# OBKP_Effector_PCB.net
KiCad netlist of a schematic drawn in EAGLE
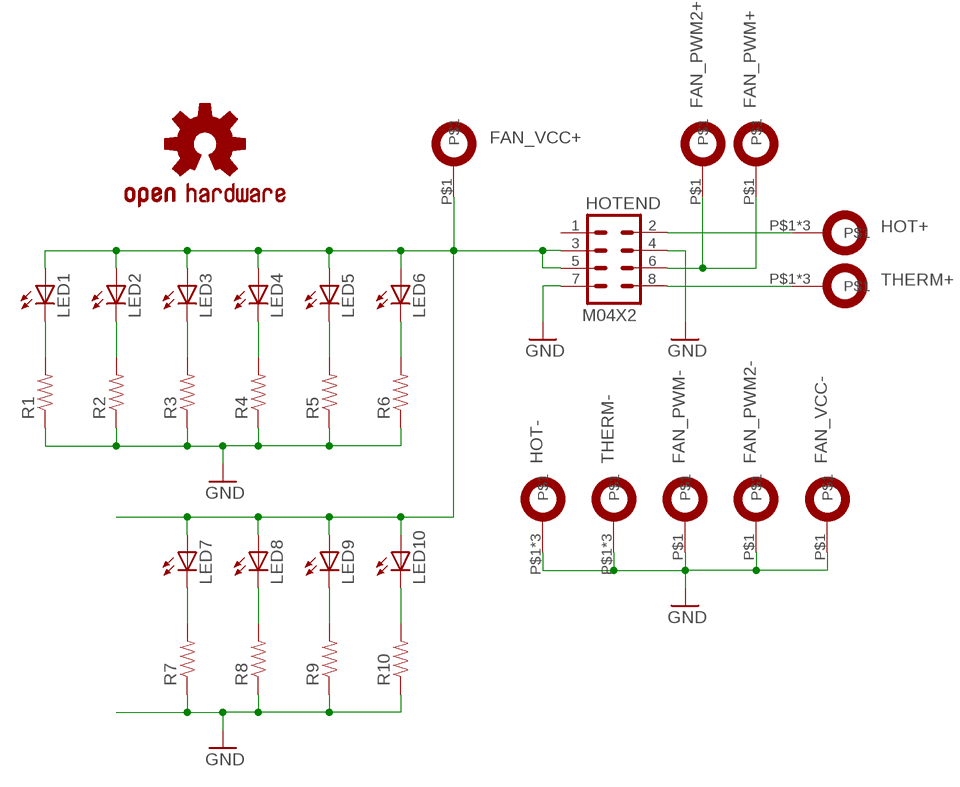
[diagram p0: schematic, sheet 1]

(export (version "E")
  (design (tool "Eeschema 10.0.6"))
  (components
    (comp (ref "FAN_PWM+")
      (value "LUG2.3")
      (footprint "eagle-import:2.3MM")
      (libsource (lib "eagle-import") (part "LUG2.3"))
    )
    (comp (ref "FAN_PWM-")
      (value "LUG2.3")
      (footprint "eagle-import:2.3MM")
      (libsource (lib "eagle-import") (part "LUG2.3"))
    )
    (comp (ref "FAN_PWM2+")
      (value "LUG2.3")
      (footprint "eagle-import:2.3MM")
      (libsource (lib "eagle-import") (part "LUG2.3"))
    )
    (comp (ref "FAN_PWM2-")
      (value "LUG2.3")
      (footprint "eagle-import:2.3MM")
      (libsource (lib "eagle-import") (part "LUG2.3"))
    )
    (comp (ref "FAN_VCC+")
      (value "LUG2.3")
      (footprint "eagle-import:2.3MM")
      (libsource (lib "eagle-import") (part "LUG2.3"))
    )
    (comp (ref "FAN_VCC-")
      (value "LUG2.3")
      (footprint "eagle-import:2.3MM")
      (libsource (lib "eagle-import") (part "LUG2.3"))
    )
    (comp (ref "HOT+")
      (value "LUG3-X")
      (footprint "eagle-import:3MM")
      (libsource (lib "eagle-import") (part "LUG3-X"))
    )
    (comp (ref "HOT-")
      (value "LUG3-X")
      (footprint "eagle-import:3MM")
      (libsource (lib "eagle-import") (part "LUG3-X"))
    )
    (comp (ref "HOTEND")
      (value "M04X2")
      (footprint "eagle-import:2X4")
      (libsource (lib "eagle-import") (part "M04X2"))
    )
    (comp (ref "LED1")
      (value "LED0805")
      (footprint "eagle-import:CHIPLED_0805")
      (libsource (lib "eagle-import") (part "LED0805"))
    )
    (comp (ref "LED2")
      (value "LED0805")
      (footprint "eagle-import:CHIPLED_0805")
      (libsource (lib "eagle-import") (part "LED0805"))
    )
    (comp (ref "LED3")
      (value "LED0805")
      (footprint "eagle-import:CHIPLED_0805")
      (libsource (lib "eagle-import") (part "LED0805"))
    )
    (comp (ref "LED4")
      (value "LED0805")
      (footprint "eagle-import:CHIPLED_0805")
      (libsource (lib "eagle-import") (part "LED0805"))
    )
    (comp (ref "LED5")
      (value "LED0805")
      (footprint "eagle-import:CHIPLED_0805")
      (libsource (lib "eagle-import") (part "LED0805"))
    )
    (comp (ref "LED6")
      (value "LED0805")
      (footprint "eagle-import:CHIPLED_0805")
      (libsource (lib "eagle-import") (part "LED0805"))
    )
    (comp (ref "LED7")
      (value "LED0805")
      (footprint "eagle-import:CHIPLED_0805")
      (libsource (lib "eagle-import") (part "LED0805"))
    )
    (comp (ref "LED8")
      (value "LED0805")
      (footprint "eagle-import:CHIPLED_0805")
      (libsource (lib "eagle-import") (part "LED0805"))
    )
    (comp (ref "LED9")
      (value "LED0805")
      (footprint "eagle-import:CHIPLED_0805")
      (libsource (lib "eagle-import") (part "LED0805"))
    )
    (comp (ref "LED10")
      (value "LED0805")
      (footprint "eagle-import:CHIPLED_0805")
      (libsource (lib "eagle-import") (part "LED0805"))
    )
    (comp (ref "LOGO1")
      (value "OSHW-LOGOS")
      (footprint "eagle-import:OSHW-LOGO-S")
      (libsource (lib "eagle-import") (part "OSHW-LOGOS"))
    )
    (comp (ref "R1")
      (value "RESISTOR0805-RES")
      (footprint "eagle-import:0805")
      (libsource (lib "eagle-import") (part "RESISTOR0805-RES"))
    )
    (comp (ref "R2")
      (value "RESISTOR0805-RES")
      (footprint "eagle-import:0805")
      (libsource (lib "eagle-import") (part "RESISTOR0805-RES"))
    )
    (comp (ref "R3")
      (value "RESISTOR0805-RES")
      (footprint "eagle-import:0805")
      (libsource (lib "eagle-import") (part "RESISTOR0805-RES"))
    )
    (comp (ref "R4")
      (value "RESISTOR0805-RES")
      (footprint "eagle-import:0805")
      (libsource (lib "eagle-import") (part "RESISTOR0805-RES"))
    )
    (comp (ref "R5")
      (value "RESISTOR0805-RES")
      (footprint "eagle-import:0805")
      (libsource (lib "eagle-import") (part "RESISTOR0805-RES"))
    )
    (comp (ref "R6")
      (value "RESISTOR0805-RES")
      (footprint "eagle-import:0805")
      (libsource (lib "eagle-import") (part "RESISTOR0805-RES"))
    )
    (comp (ref "R7")
      (value "RESISTOR0805-RES")
      (footprint "eagle-import:0805")
      (libsource (lib "eagle-import") (part "RESISTOR0805-RES"))
    )
    (comp (ref "R8")
      (value "RESISTOR0805-RES")
      (footprint "eagle-import:0805")
      (libsource (lib "eagle-import") (part "RESISTOR0805-RES"))
    )
    (comp (ref "R9")
      (value "RESISTOR0805-RES")
      (footprint "eagle-import:0805")
      (libsource (lib "eagle-import") (part "RESISTOR0805-RES"))
    )
    (comp (ref "R10")
      (value "RESISTOR0805-RES")
      (footprint "eagle-import:0805")
      (libsource (lib "eagle-import") (part "RESISTOR0805-RES"))
    )
    (comp (ref "THERM+")
      (value "LUG3-X")
      (footprint "eagle-import:3MM")
      (libsource (lib "eagle-import") (part "LUG3-X"))
    )
    (comp (ref "THERM-")
      (value "LUG3-X")
      (footprint "eagle-import:3MM")
      (libsource (lib "eagle-import") (part "LUG3-X"))
    )
  )
  (nets
    (net (code "1") (name "GND") (class "Default")
      (node (ref "FAN_PWM-") (pin "P$1") (pinfunction "P$1_P$1") (pintype "bidirectional"))
      (node (ref "FAN_PWM2-") (pin "P$1") (pinfunction "P$1_P$1") (pintype "bidirectional"))
      (node (ref "FAN_VCC-") (pin "P$1") (pinfunction "P$1_P$1") (pintype "bidirectional"))
      (node (ref "HOT-") (pin "P$1") (pinfunction "P$1_P$1") (pintype "bidirectional"))
      (node (ref "HOT-") (pin "P$2") (pinfunction "P$1_P$2") (pintype "bidirectional"))
      (node (ref "HOT-") (pin "P$3") (pinfunction "P$1_P$3") (pintype "bidirectional"))
      (node (ref "HOTEND") (pin "4") (pinfunction "4_4") (pintype "passive"))
      (node (ref "HOTEND") (pin "7") (pinfunction "7_7") (pintype "passive"))
      (node (ref "R1") (pin "1") (pinfunction "1_1") (pintype "passive"))
      (node (ref "R10") (pin "1") (pinfunction "1_1") (pintype "passive"))
      (node (ref "R2") (pin "1") (pinfunction "1_1") (pintype "passive"))
      (node (ref "R3") (pin "1") (pinfunction "1_1") (pintype "passive"))
      (node (ref "R4") (pin "1") (pinfunction "1_1") (pintype "passive"))
      (node (ref "R5") (pin "1") (pinfunction "1_1") (pintype "passive"))
      (node (ref "R6") (pin "1") (pinfunction "1_1") (pintype "passive"))
      (node (ref "R7") (pin "1") (pinfunction "1_1") (pintype "passive"))
      (node (ref "R8") (pin "1") (pinfunction "1_1") (pintype "passive"))
      (node (ref "R9") (pin "1") (pinfunction "1_1") (pintype "passive"))
      (node (ref "THERM-") (pin "P$1") (pinfunction "P$1_P$1") (pintype "bidirectional"))
      (node (ref "THERM-") (pin "P$2") (pinfunction "P$1_P$2") (pintype "bidirectional"))
      (node (ref "THERM-") (pin "P$3") (pinfunction "P$1_P$3") (pintype "bidirectional"))
    )
    (net (code "2") (name "Net-(FAN_PWM+-PadP$1)") (class "Default")
      (node (ref "FAN_PWM+") (pin "P$1") (pinfunction "P$1_P$1") (pintype "bidirectional"))
      (node (ref "FAN_PWM2+") (pin "P$1") (pinfunction "P$1_P$1") (pintype "bidirectional"))
      (node (ref "HOTEND") (pin "6") (pinfunction "6_6") (pintype "passive"))
    )
    (net (code "3") (name "Net-(FAN_VCC+-PadP$1)") (class "Default")
      (node (ref "FAN_VCC+") (pin "P$1") (pinfunction "P$1_P$1") (pintype "bidirectional"))
      (node (ref "HOTEND") (pin "3") (pinfunction "3_3") (pintype "passive"))
      (node (ref "HOTEND") (pin "5") (pinfunction "5_5") (pintype "passive"))
      (node (ref "LED1") (pin "A") (pinfunction "A_A") (pintype "passive"))
      (node (ref "LED10") (pin "A") (pinfunction "A_A") (pintype "passive"))
      (node (ref "LED2") (pin "A") (pinfunction "A_A") (pintype "passive"))
      (node (ref "LED3") (pin "A") (pinfunction "A_A") (pintype "passive"))
      (node (ref "LED4") (pin "A") (pinfunction "A_A") (pintype "passive"))
      (node (ref "LED5") (pin "A") (pinfunction "A_A") (pintype "passive"))
      (node (ref "LED6") (pin "A") (pinfunction "A_A") (pintype "passive"))
      (node (ref "LED7") (pin "A") (pinfunction "A_A") (pintype "passive"))
      (node (ref "LED8") (pin "A") (pinfunction "A_A") (pintype "passive"))
      (node (ref "LED9") (pin "A") (pinfunction "A_A") (pintype "passive"))
    )
    (net (code "4") (name "Net-(HOT+-P$1-PadP$2)") (class "Default")
      (node (ref "HOT+") (pin "P$1") (pinfunction "P$1_P$1") (pintype "bidirectional"))
      (node (ref "HOT+") (pin "P$2") (pinfunction "P$1_P$2") (pintype "bidirectional"))
      (node (ref "HOT+") (pin "P$3") (pinfunction "P$1_P$3") (pintype "bidirectional"))
      (node (ref "HOTEND") (pin "2") (pinfunction "2_2") (pintype "passive"))
    )
    (net (code "5") (name "Net-(HOTEND-Pad8)") (class "Default")
      (node (ref "HOTEND") (pin "8") (pinfunction "8_8") (pintype "passive"))
      (node (ref "THERM+") (pin "P$1") (pinfunction "P$1_P$1") (pintype "bidirectional"))
      (node (ref "THERM+") (pin "P$2") (pinfunction "P$1_P$2") (pintype "bidirectional"))
      (node (ref "THERM+") (pin "P$3") (pinfunction "P$1_P$3") (pintype "bidirectional"))
    )
    (net (code "6") (name "Net-(LED1-PadC)") (class "Default")
      (node (ref "LED1") (pin "C") (pinfunction "C_C") (pintype "passive"))
      (node (ref "R1") (pin "2") (pinfunction "2_2") (pintype "passive"))
    )
    (net (code "7") (name "Net-(LED2-PadC)") (class "Default")
      (node (ref "LED2") (pin "C") (pinfunction "C_C") (pintype "passive"))
      (node (ref "R2") (pin "2") (pinfunction "2_2") (pintype "passive"))
    )
    (net (code "8") (name "Net-(LED3-PadC)") (class "Default")
      (node (ref "LED3") (pin "C") (pinfunction "C_C") (pintype "passive"))
      (node (ref "R3") (pin "2") (pinfunction "2_2") (pintype "passive"))
    )
    (net (code "9") (name "Net-(LED4-PadC)") (class "Default")
      (node (ref "LED4") (pin "C") (pinfunction "C_C") (pintype "passive"))
      (node (ref "R4") (pin "2") (pinfunction "2_2") (pintype "passive"))
    )
    (net (code "10") (name "Net-(LED5-PadC)") (class "Default")
      (node (ref "LED5") (pin "C") (pinfunction "C_C") (pintype "passive"))
      (node (ref "R5") (pin "2") (pinfunction "2_2") (pintype "passive"))
    )
    (net (code "11") (name "Net-(LED6-PadC)") (class "Default")
      (node (ref "LED6") (pin "C") (pinfunction "C_C") (pintype "passive"))
      (node (ref "R6") (pin "2") (pinfunction "2_2") (pintype "passive"))
    )
    (net (code "12") (name "Net-(LED7-PadC)") (class "Default")
      (node (ref "LED7") (pin "C") (pinfunction "C_C") (pintype "passive"))
      (node (ref "R7") (pin "2") (pinfunction "2_2") (pintype "passive"))
    )
    (net (code "13") (name "Net-(LED8-PadC)") (class "Default")
      (node (ref "LED8") (pin "C") (pinfunction "C_C") (pintype "passive"))
      (node (ref "R8") (pin "2") (pinfunction "2_2") (pintype "passive"))
    )
    (net (code "14") (name "Net-(LED9-PadC)") (class "Default")
      (node (ref "LED9") (pin "C") (pinfunction "C_C") (pintype "passive"))
      (node (ref "R9") (pin "2") (pinfunction "2_2") (pintype "passive"))
    )
    (net (code "15") (name "Net-(LED10-PadC)") (class "Default")
      (node (ref "LED10") (pin "C") (pinfunction "C_C") (pintype "passive"))
      (node (ref "R10") (pin "2") (pinfunction "2_2") (pintype "passive"))
    )
    (net (code "16") (name "unconnected-(HOTEND-Pad1)") (class "Default")
      (node (ref "HOTEND") (pin "1") (pinfunction "1_1") (pintype "passive"))
    )
  )
)
